# atmega48A_dip.net
KiCad netlist of a schematic drawn in EAGLE
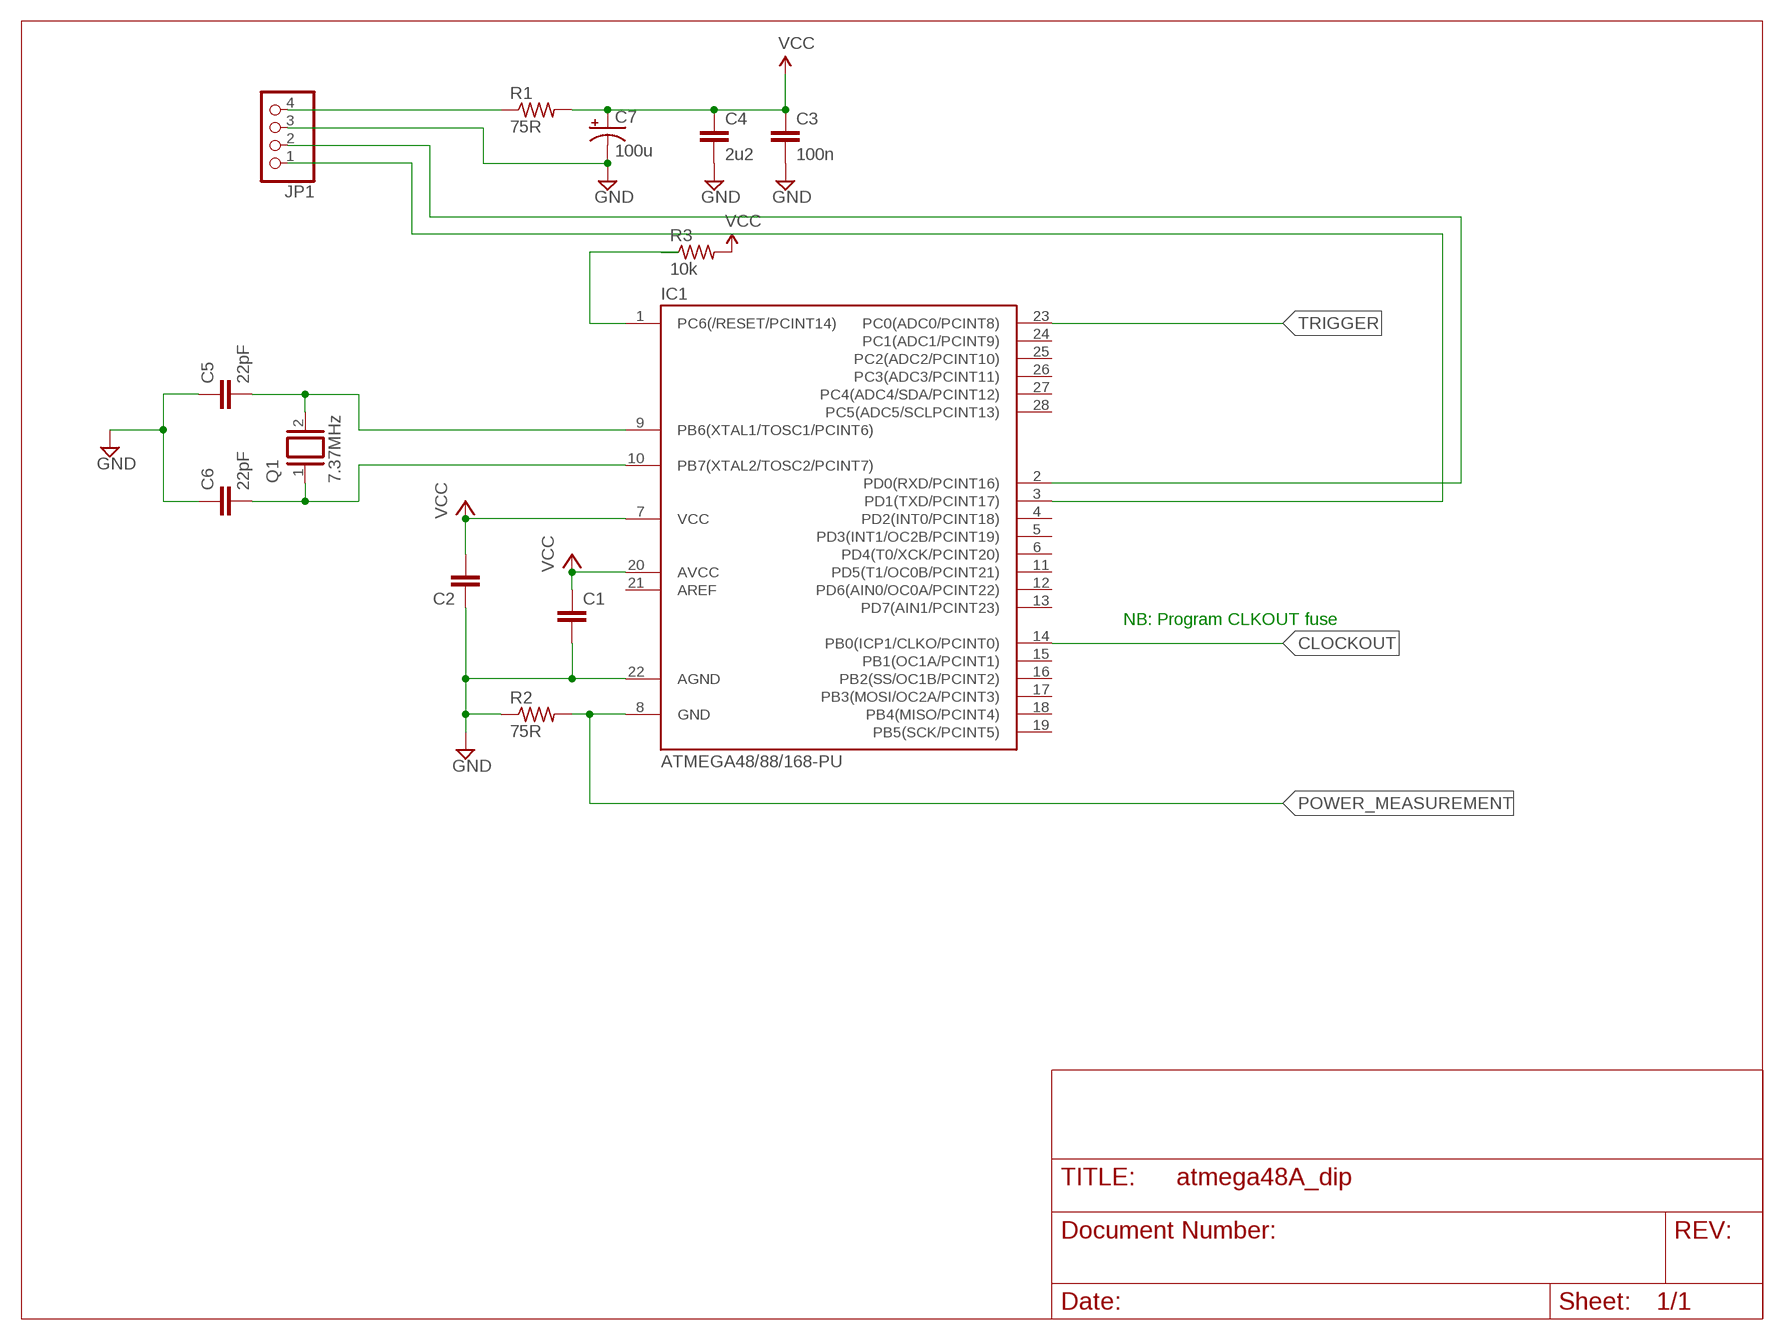
[diagram p0: schematic, sheet 1]

(export (version "E")
  (design (tool "Eeschema 10.0.6"))
  (components
    (comp (ref "C1")
      (value "C-EUC0805")
      (footprint "eagle-import:C0805")
      (libsource (lib "eagle-import") (part "C-EUC0805"))
    )
    (comp (ref "C2")
      (value "C-EUC0805")
      (footprint "eagle-import:C0805")
      (libsource (lib "eagle-import") (part "C-EUC0805"))
    )
    (comp (ref "C3")
      (value "100n")
      (footprint "eagle-import:C0805")
      (libsource (lib "eagle-import") (part "C-EUC0805"))
    )
    (comp (ref "C4")
      (value "2u2")
      (footprint "eagle-import:C0805")
      (libsource (lib "eagle-import") (part "C-EUC0805"))
    )
    (comp (ref "C5")
      (value "22pF")
      (footprint "eagle-import:C0805")
      (libsource (lib "eagle-import") (part "C-EUC0805"))
    )
    (comp (ref "C6")
      (value "22pF")
      (footprint "eagle-import:C0805")
      (libsource (lib "eagle-import") (part "C-EUC0805"))
    )
    (comp (ref "C7")
      (value "100u")
      (footprint "eagle-import:140CLH-0810")
      (libsource (lib "eagle-import") (part "CPOL-US140CLH-0810"))
    )
    (comp (ref "IC1")
      (value "ATMEGA48/88/168-PU")
      (footprint "eagle-import:DIL28-3")
      (libsource (lib "eagle-import") (part "ATMEGA48/88/168-PU"))
    )
    (comp (ref "JP1")
      (value "PINHD-1X4/90")
      (footprint "eagle-import:1X04_90")
      (libsource (lib "eagle-import") (part "PINHD-1X4/90"))
    )
    (comp (ref "Q1")
      (value "7.37MHz")
      (footprint "eagle-import:Q")
      (libsource (lib "eagle-import") (part "XTAL"))
    )
    (comp (ref "R1")
      (value "75R")
      (footprint "eagle-import:M0805")
      (libsource (lib "eagle-import") (part "R-US_M0805"))
    )
    (comp (ref "R2")
      (value "75R")
      (footprint "eagle-import:R0805")
      (libsource (lib "eagle-import") (part "resistor_R-US_R0805"))
    )
    (comp (ref "R3")
      (value "10k")
      (footprint "eagle-import:M0805")
      (libsource (lib "eagle-import") (part "R-US_M0805"))
    )
  )
  (nets
    (net (code "1") (name "CLOCKOUT") (class "Default")
      (node (ref "IC1") (pin "14") (pinfunction "PB0(ICP1/CLKO/PCINT0)_14") (pintype "bidirectional"))
    )
    (net (code "2") (name "GND") (class "Default")
      (node (ref "C1") (pin "2") (pinfunction "2_2") (pintype "passive"))
      (node (ref "C2") (pin "1") (pinfunction "1_1") (pintype "passive"))
      (node (ref "C3") (pin "2") (pinfunction "2_2") (pintype "passive"))
      (node (ref "C4") (pin "2") (pinfunction "2_2") (pintype "passive"))
      (node (ref "C5") (pin "1") (pinfunction "1_1") (pintype "passive"))
      (node (ref "C6") (pin "1") (pinfunction "1_1") (pintype "passive"))
      (node (ref "C7") (pin "-") (pinfunction "-_-") (pintype "passive"))
      (node (ref "IC1") (pin "22") (pinfunction "AGND_22") (pintype "power_in"))
      (node (ref "JP1") (pin "3") (pinfunction "3_3") (pintype "passive"))
      (node (ref "R2") (pin "1") (pinfunction "1_1") (pintype "passive"))
    )
    (net (code "3") (name "Net-(IC1-PB6(XTAL1{slash}TOSC1{slash}PCINT6))") (class "Default")
      (node (ref "C5") (pin "2") (pinfunction "2_2") (pintype "passive"))
      (node (ref "IC1") (pin "9") (pinfunction "PB6(XTAL1/TOSC1/PCINT6)_9") (pintype "bidirectional"))
      (node (ref "Q1") (pin "2") (pinfunction "2_2") (pintype "passive"))
    )
    (net (code "4") (name "Net-(IC1-PB7(XTAL2{slash}TOSC2{slash}PCINT7))") (class "Default")
      (node (ref "C6") (pin "2") (pinfunction "2_2") (pintype "passive"))
      (node (ref "IC1") (pin "10") (pinfunction "PB7(XTAL2/TOSC2/PCINT7)_10") (pintype "bidirectional"))
      (node (ref "Q1") (pin "1") (pinfunction "1_1") (pintype "passive"))
    )
    (net (code "5") (name "Net-(IC1-PD0(RXD{slash}PCINT16))") (class "Default")
      (node (ref "IC1") (pin "2") (pinfunction "PD0(RXD/PCINT16)_2") (pintype "bidirectional"))
      (node (ref "JP1") (pin "2") (pinfunction "2_2") (pintype "passive"))
    )
    (net (code "6") (name "Net-(IC1-PD1(TXD{slash}PCINT17))") (class "Default")
      (node (ref "IC1") (pin "3") (pinfunction "PD1(TXD/PCINT17)_3") (pintype "bidirectional"))
      (node (ref "JP1") (pin "1") (pinfunction "1_1") (pintype "passive"))
    )
    (net (code "7") (name "Net-(JP1-Pad4)") (class "Default")
      (node (ref "JP1") (pin "4") (pinfunction "4_4") (pintype "passive"))
      (node (ref "R1") (pin "1") (pinfunction "1_1") (pintype "passive"))
    )
    (net (code "8") (name "POWER_MEASUREMENT") (class "Default")
      (node (ref "IC1") (pin "8") (pinfunction "GND_8") (pintype "power_in"))
      (node (ref "R2") (pin "2") (pinfunction "2_2") (pintype "passive"))
    )
    (net (code "9") (name "TRIGGER") (class "Default")
      (node (ref "IC1") (pin "23") (pinfunction "PC0(ADC0/PCINT8)_23") (pintype "bidirectional"))
    )
    (net (code "10") (name "VCC") (class "Default")
      (node (ref "C1") (pin "1") (pinfunction "1_1") (pintype "passive"))
      (node (ref "C2") (pin "2") (pinfunction "2_2") (pintype "passive"))
      (node (ref "C3") (pin "1") (pinfunction "1_1") (pintype "passive"))
      (node (ref "C4") (pin "1") (pinfunction "1_1") (pintype "passive"))
      (node (ref "C7") (pin "+") (pinfunction "+_+") (pintype "passive"))
      (node (ref "IC1") (pin "20") (pinfunction "AVCC_20") (pintype "passive"))
      (node (ref "IC1") (pin "7") (pinfunction "VCC_7") (pintype "power_in"))
      (node (ref "R1") (pin "2") (pinfunction "2_2") (pintype "passive"))
      (node (ref "R3") (pin "2") (pinfunction "2_2") (pintype "passive"))
    )
    (net (code "11") (name "unconnected-(IC1-AREF-Pad21)") (class "Default")
      (node (ref "IC1") (pin "21") (pinfunction "AREF_21") (pintype "passive"))
    )
    (net (code "12") (name "unconnected-(IC1-PB1(OC1A{slash}PCINT1)-Pad15)") (class "Default")
      (node (ref "IC1") (pin "15") (pinfunction "PB1(OC1A/PCINT1)_15") (pintype "bidirectional"))
    )
    (net (code "13") (name "unconnected-(IC1-PB2(SS{slash}OC1B{slash}PCINT2)-Pad16)") (class "Default")
      (node (ref "IC1") (pin "16") (pinfunction "PB2(SS/OC1B/PCINT2)_16") (pintype "bidirectional"))
    )
    (net (code "14") (name "unconnected-(IC1-PB3(MOSI{slash}OC2A{slash}PCINT3)-Pad17)") (class "Default")
      (node (ref "IC1") (pin "17") (pinfunction "PB3(MOSI/OC2A/PCINT3)_17") (pintype "bidirectional"))
    )
    (net (code "15") (name "unconnected-(IC1-PB4(MISO{slash}PCINT4)-Pad18)") (class "Default")
      (node (ref "IC1") (pin "18") (pinfunction "PB4(MISO/PCINT4)_18") (pintype "bidirectional"))
    )
    (net (code "16") (name "unconnected-(IC1-PB5(SCK{slash}PCINT5)-Pad19)") (class "Default")
      (node (ref "IC1") (pin "19") (pinfunction "PB5(SCK/PCINT5)_19") (pintype "bidirectional"))
    )
    (net (code "17") (name "unconnected-(IC1-PC1(ADC1{slash}PCINT9)-Pad24)") (class "Default")
      (node (ref "IC1") (pin "24") (pinfunction "PC1(ADC1/PCINT9)_24") (pintype "bidirectional"))
    )
    (net (code "18") (name "unconnected-(IC1-PC2(ADC2{slash}PCINT10)-Pad25)") (class "Default")
      (node (ref "IC1") (pin "25") (pinfunction "PC2(ADC2/PCINT10)_25") (pintype "bidirectional"))
    )
    (net (code "19") (name "unconnected-(IC1-PC3(ADC3{slash}PCINT11)-Pad26)") (class "Default")
      (node (ref "IC1") (pin "26") (pinfunction "PC3(ADC3/PCINT11)_26") (pintype "bidirectional"))
    )
    (net (code "20") (name "unconnected-(IC1-PC4(ADC4{slash}SDA{slash}PCINT12)-Pad27)") (class "Default")
      (node (ref "IC1") (pin "27") (pinfunction "PC4(ADC4/SDA/PCINT12)_27") (pintype "bidirectional"))
    )
    (net (code "21") (name "unconnected-(IC1-PC5(ADC5{slash}SCLPCINT13)-Pad28)") (class "Default")
      (node (ref "IC1") (pin "28") (pinfunction "PC5(ADC5/SCLPCINT13)_28") (pintype "bidirectional"))
    )
    (net (code "22") (name "unconnected-(IC1-PC6({slash}RESET{slash}PCINT14)-Pad1)") (class "Default")
      (node (ref "IC1") (pin "1") (pinfunction "PC6(/RESET/PCINT14)_1") (pintype "bidirectional"))
    )
    (net (code "23") (name "unconnected-(IC1-PD2(INT0{slash}PCINT18)-Pad4)") (class "Default")
      (node (ref "IC1") (pin "4") (pinfunction "PD2(INT0/PCINT18)_4") (pintype "bidirectional"))
    )
    (net (code "24") (name "unconnected-(IC1-PD3(INT1{slash}OC2B{slash}PCINT19)-Pad5)") (class "Default")
      (node (ref "IC1") (pin "5") (pinfunction "PD3(INT1/OC2B/PCINT19)_5") (pintype "bidirectional"))
    )
    (net (code "25") (name "unconnected-(IC1-PD4(T0{slash}XCK{slash}PCINT20)-Pad6)") (class "Default")
      (node (ref "IC1") (pin "6") (pinfunction "PD4(T0/XCK/PCINT20)_6") (pintype "bidirectional"))
    )
    (net (code "26") (name "unconnected-(IC1-PD5(T1{slash}OC0B{slash}PCINT21)-Pad11)") (class "Default")
      (node (ref "IC1") (pin "11") (pinfunction "PD5(T1/OC0B/PCINT21)_11") (pintype "bidirectional"))
    )
    (net (code "27") (name "unconnected-(IC1-PD6(AIN0{slash}OC0A{slash}PCINT22)-Pad12)") (class "Default")
      (node (ref "IC1") (pin "12") (pinfunction "PD6(AIN0/OC0A/PCINT22)_12") (pintype "bidirectional"))
    )
    (net (code "28") (name "unconnected-(IC1-PD7(AIN1{slash}PCINT23)-Pad13)") (class "Default")
      (node (ref "IC1") (pin "13") (pinfunction "PD7(AIN1/PCINT23)_13") (pintype "bidirectional"))
    )
    (net (code "29") (name "unconnected-(R3-Pad1)") (class "Default")
      (node (ref "R3") (pin "1") (pinfunction "1_1") (pintype "passive"))
    )
  )
)
